# MP3426.net
KiCad netlist of a schematic drawn in EasyEDA Pro
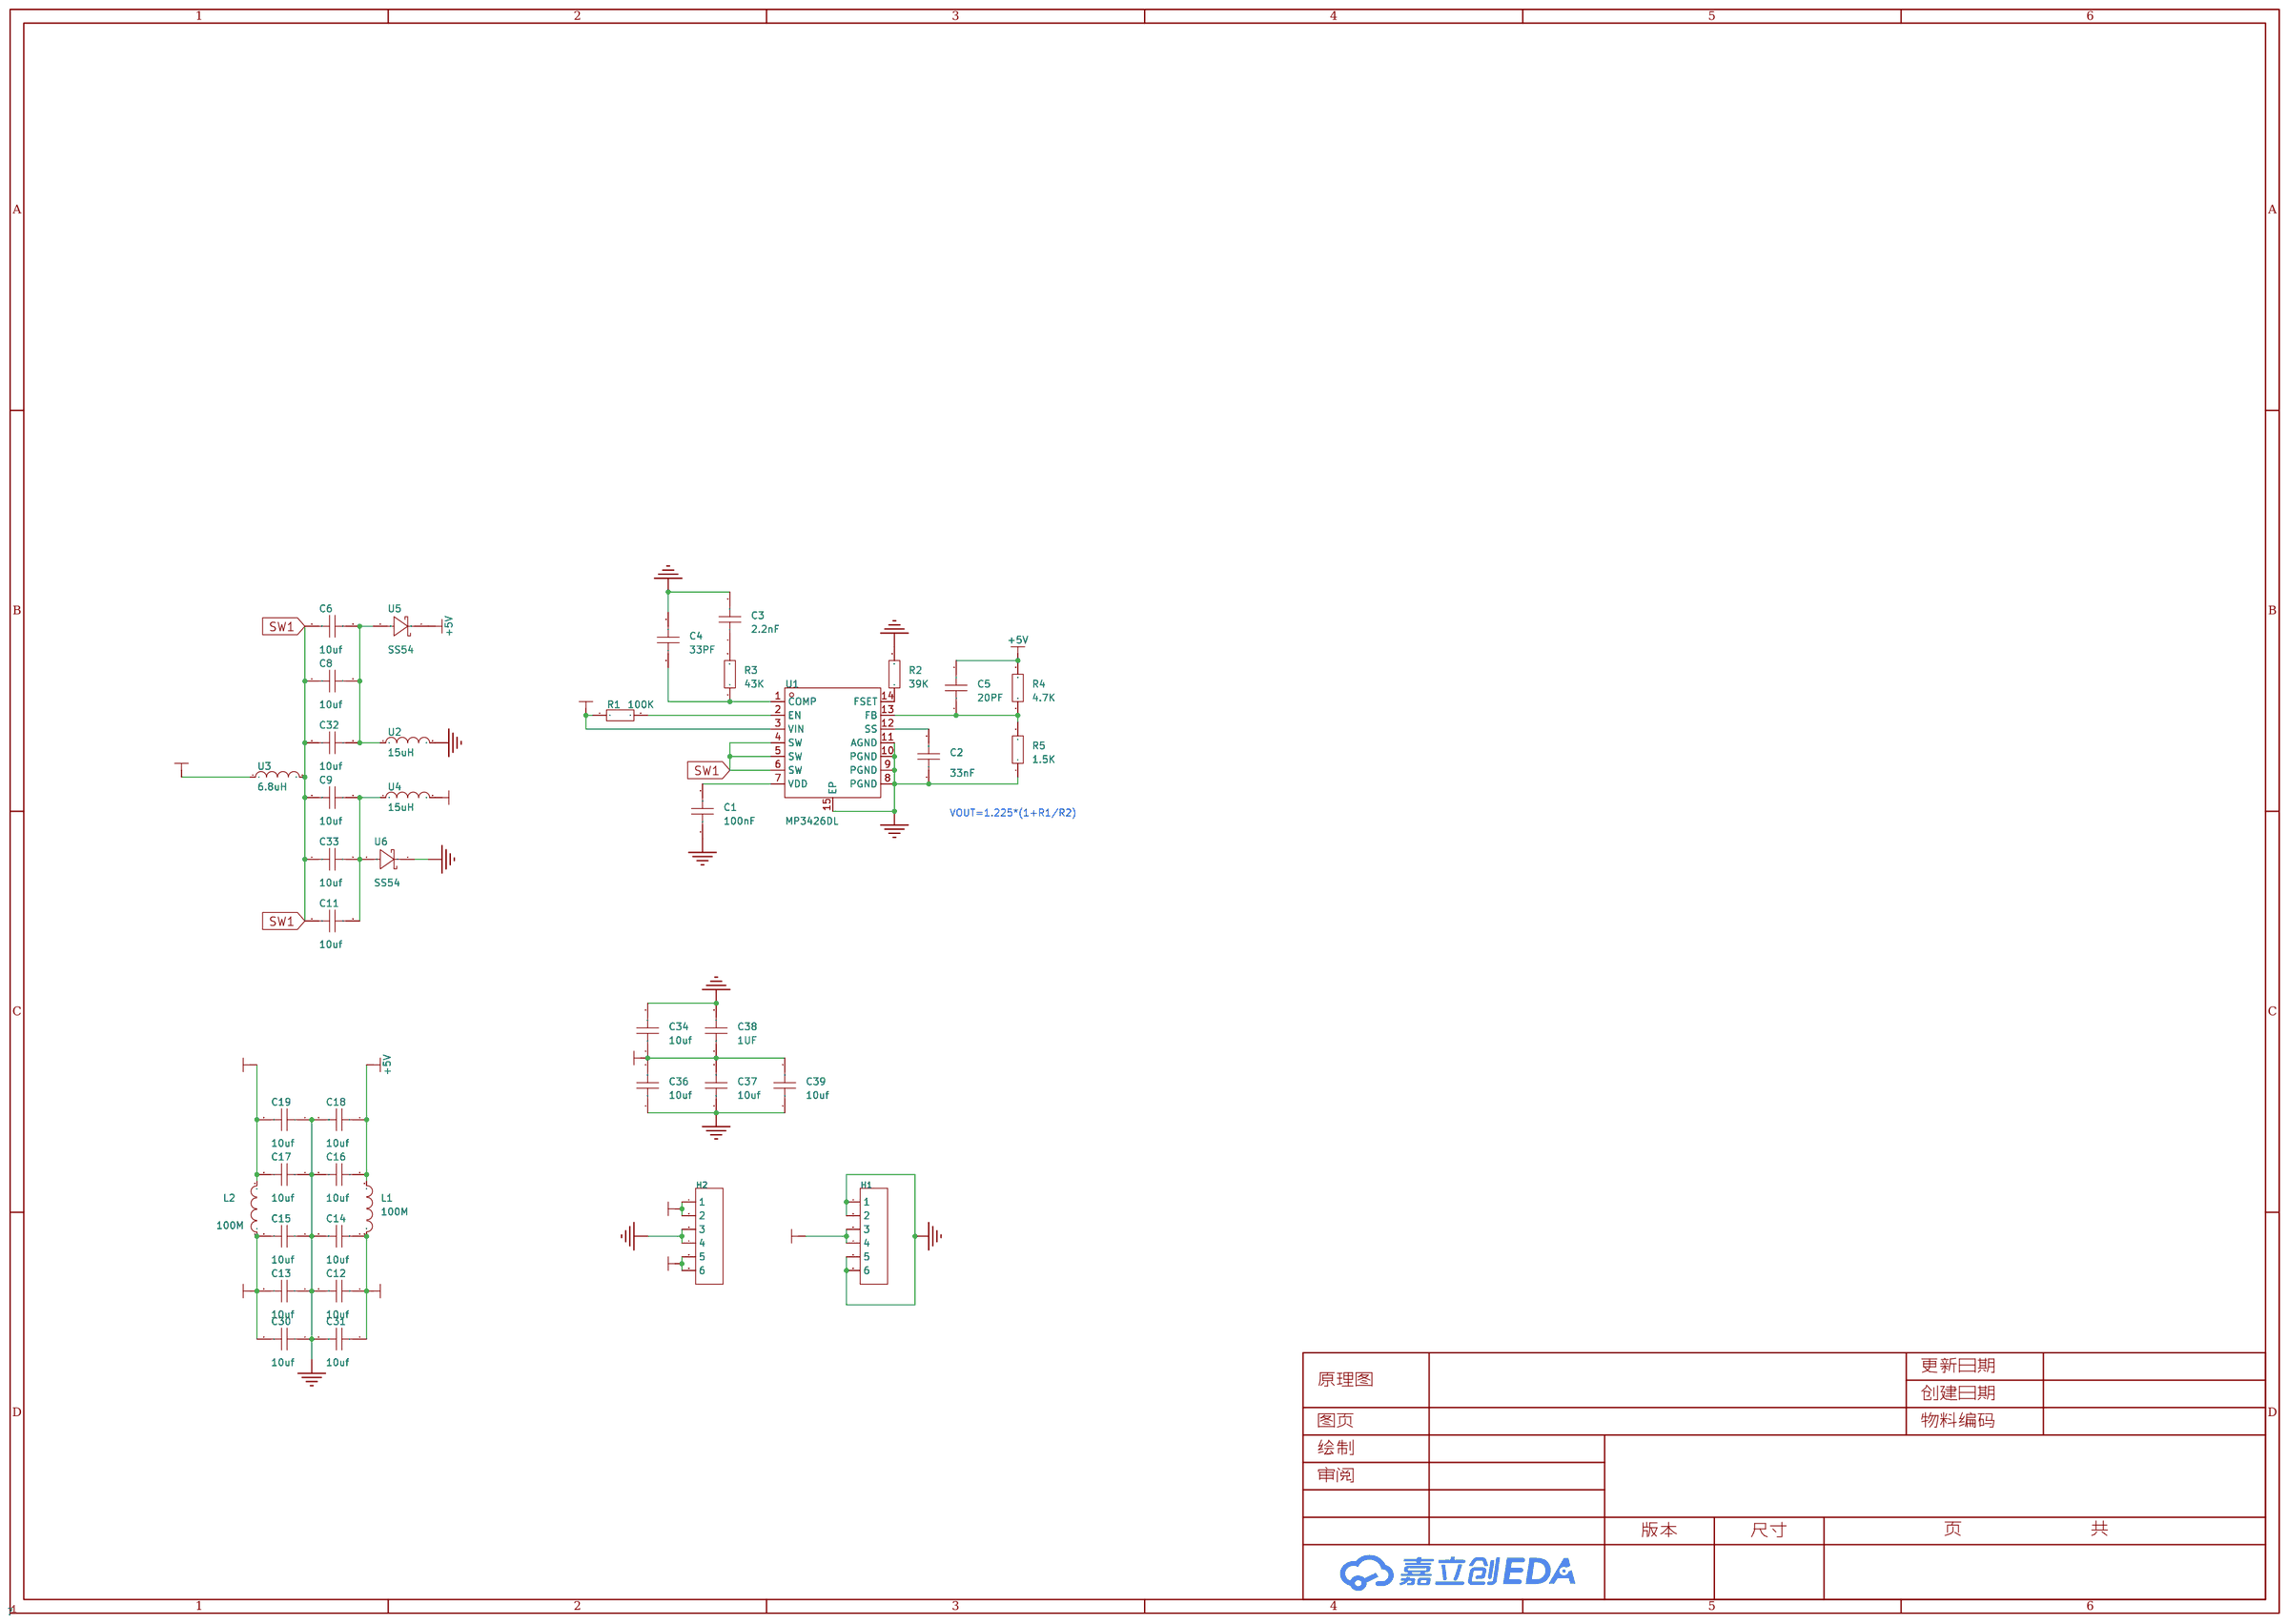
[diagram p0: schematic sheet]

(export (version "E")
  (design (tool "Eeschema 10.0.6"))
  (components
    (comp (ref "C1")
      (value "100nF")
      (footprint "easyedapro:C1206")
      (libsource (lib "easyedapro") (part "CapAcitance"))
    )
    (comp (ref "C2")
      (value "33nF")
      (footprint "easyedapro:C1206")
      (libsource (lib "easyedapro") (part "CapAcitance"))
    )
    (comp (ref "C3")
      (value "2.2nF")
      (footprint "easyedapro:C1206")
      (libsource (lib "easyedapro") (part "CapAcitance"))
    )
    (comp (ref "C4")
      (value "33PF")
      (footprint "easyedapro:C1206")
      (libsource (lib "easyedapro") (part "CapAcitance"))
    )
    (comp (ref "C5")
      (value "20PF")
      (footprint "easyedapro:C1206")
      (libsource (lib "easyedapro") (part "CapAcitance"))
    )
    (comp (ref "C6")
      (value "10uf")
      (footprint "easyedapro:C1206")
      (libsource (lib "easyedapro") (part "CapAcitance"))
    )
    (comp (ref "C8")
      (value "10uf")
      (footprint "easyedapro:C1206")
      (libsource (lib "easyedapro") (part "CapAcitance"))
    )
    (comp (ref "C9")
      (value "10uf")
      (footprint "easyedapro:C1206")
      (libsource (lib "easyedapro") (part "CapAcitance"))
    )
    (comp (ref "C11")
      (value "10uf")
      (footprint "easyedapro:C1206")
      (libsource (lib "easyedapro") (part "CapAcitance"))
    )
    (comp (ref "C12")
      (value "10uf")
      (footprint "easyedapro:C1206")
      (libsource (lib "easyedapro") (part "CapAcitance"))
    )
    (comp (ref "C13")
      (value "10uf")
      (footprint "easyedapro:C1206")
      (libsource (lib "easyedapro") (part "CapAcitance"))
    )
    (comp (ref "C14")
      (value "10uf")
      (footprint "easyedapro:C1206")
      (libsource (lib "easyedapro") (part "CapAcitance"))
    )
    (comp (ref "C15")
      (value "10uf")
      (footprint "easyedapro:C1206")
      (libsource (lib "easyedapro") (part "CapAcitance"))
    )
    (comp (ref "C16")
      (value "10uf")
      (footprint "easyedapro:C1206")
      (libsource (lib "easyedapro") (part "CapAcitance"))
    )
    (comp (ref "C17")
      (value "10uf")
      (footprint "easyedapro:C1206")
      (libsource (lib "easyedapro") (part "CapAcitance"))
    )
    (comp (ref "C18")
      (value "10uf")
      (footprint "easyedapro:C1206")
      (libsource (lib "easyedapro") (part "CapAcitance"))
    )
    (comp (ref "C19")
      (value "10uf")
      (footprint "easyedapro:C1206")
      (libsource (lib "easyedapro") (part "CapAcitance"))
    )
    (comp (ref "C30")
      (value "10uf")
      (footprint "easyedapro:C1206")
      (libsource (lib "easyedapro") (part "CapAcitance"))
    )
    (comp (ref "C31")
      (value "10uf")
      (footprint "easyedapro:C1206")
      (libsource (lib "easyedapro") (part "CapAcitance"))
    )
    (comp (ref "C32")
      (value "10uf")
      (footprint "easyedapro:C1206")
      (libsource (lib "easyedapro") (part "CapAcitance"))
    )
    (comp (ref "C33")
      (value "10uf")
      (footprint "easyedapro:C1206")
      (libsource (lib "easyedapro") (part "CapAcitance"))
    )
    (comp (ref "C34")
      (value "10uf")
      (footprint "easyedapro:C1206")
      (libsource (lib "easyedapro") (part "CapAcitance"))
    )
    (comp (ref "C36")
      (value "10uf")
      (footprint "easyedapro:C1206")
      (libsource (lib "easyedapro") (part "CapAcitance"))
    )
    (comp (ref "C37")
      (value "10uf")
      (footprint "easyedapro:C1206")
      (libsource (lib "easyedapro") (part "CapAcitance"))
    )
    (comp (ref "C38")
      (value "1UF")
      (footprint "easyedapro:C1206")
      (libsource (lib "easyedapro") (part "CapAcitance"))
    )
    (comp (ref "C39")
      (value "10uf")
      (footprint "easyedapro:C1206")
      (libsource (lib "easyedapro") (part "CapAcitance"))
    )
    (comp (ref "H1")
      (value "~")
      (footprint "easyedapro:HDR-TH_6P-P2.54-V-M-1")
      (libsource (lib "easyedapro") (part "Header-Male-2.54_1x6"))
    )
    (comp (ref "H2")
      (value "~")
      (footprint "easyedapro:HDR-TH_6P-P2.54-V-M-1")
      (libsource (lib "easyedapro") (part "Header-Male-2.54_1x6"))
    )
    (comp (ref "L1")
      (value "100M")
      (footprint "easyedapro:L1206")
      (libsource (lib "easyedapro") (part "CMI321609VR27KT"))
    )
    (comp (ref "L2")
      (value "100M")
      (footprint "easyedapro:L1206")
      (libsource (lib "easyedapro") (part "CMI321609VR27KT"))
    )
    (comp (ref "R1") (value "100K") (footprint "easyedapro:R0603") (libsource (lib "easyedapro") (part "电阻")))
    (comp (ref "R2") (value "39K") (footprint "easyedapro:R0603") (libsource (lib "easyedapro") (part "电阻")))
    (comp (ref "R3") (value "43K") (footprint "easyedapro:R0603") (libsource (lib "easyedapro") (part "电阻")))
    (comp (ref "R4") (value "4.7K") (footprint "easyedapro:R0603") (libsource (lib "easyedapro") (part "电阻")))
    (comp (ref "R5") (value "1.5K") (footprint "easyedapro:R0603") (libsource (lib "easyedapro") (part "电阻")))
    (comp (ref "U1")
      (value "MP3426DL")
      (footprint "easyedapro:DFN-14_L4.0-W3.0-P0.50-BL-EP")
      (libsource (lib "easyedapro") (part "MP3426DL"))
    )
    (comp (ref "U2")
      (value "15uH")
      (footprint "easyedapro:IND-SMD_L7.1-W6.6-1")
      (description "电感值:4.7uH;精度:±20%;额定电流:6A;饱和电流(Isat):8A;类型:一体成型电感;")
      (fields
        (field (name "Manufacturer Part") "CXP0650-4R7M-AG(4.7uh)")
        (field (name "Manufacturer") "DMBJ(振宝佳)")
      )
      (libsource (lib "easyedapro") (part "CXP0650-4R7M-AG(4.7UH)"))
    )
    (comp (ref "U3")
      (value "6.8uH")
      (footprint "easyedapro:IND-SMD_L11.0-W10.2")
      (description "电感值:22uH;精度:±20%;额定电流:5.5A;饱和电流(Isat):8A;类型:一体成型电感;")
      (fields
        (field (name "Manufacturer Part") "CXP1050-220M-AG(22uh)")
        (field (name "Manufacturer") "DMBJ(振宝佳)")
      )
      (libsource (lib "easyedapro") (part "CXP1050-220M-AG(22UH)"))
    )
    (comp (ref "U4")
      (value "15uH")
      (footprint "easyedapro:IND-SMD_L7.1-W6.6-1")
      (description "电感值:4.7uH;精度:±20%;额定电流:6A;饱和电流(Isat):8A;类型:一体成型电感;")
      (fields
        (field (name "Manufacturer Part") "CXP0650-4R7M-AG(4.7uh)")
        (field (name "Manufacturer") "DMBJ(振宝佳)")
      )
      (libsource (lib "easyedapro") (part "CXP0650-4R7M-AG(4.7UH)"))
    )
    (comp (ref "U5")
      (value "SS54")
      (footprint "easyedapro:SMB_L4.3-W3.6-LS5.4-RD")
      (description "二极管配置:独立式;正向压降(Vf):550mV@5A;直流反向耐压(Vr):40V;整流电流:5A;")
      (fields (field (name "Manufacturer") "HXY MOSFET(华轩阳电子)"))
      (libsource (lib "easyedapro") (part "SS54_C5200096"))
    )
    (comp (ref "U6")
      (value "SS54")
      (footprint "easyedapro:SMB_L4.3-W3.6-LS5.4-RD")
      (description "二极管配置:独立式;正向压降(Vf):550mV@5A;直流反向耐压(Vr):40V;整流电流:5A;")
      (fields (field (name "Manufacturer") "HXY MOSFET(华轩阳电子)"))
      (libsource (lib "easyedapro") (part "SS54_C5200096"))
    )
  )
  (nets
    (net (code "1") (name "+5V") (class "Default")
      (node (ref "C16") (pin "1") (pinfunction "1_1") (pintype "input"))
      (node (ref "C18") (pin "1") (pinfunction "1_1") (pintype "input"))
      (node (ref "C5") (pin "2") (pinfunction "2_2") (pintype "input"))
      (node (ref "L1") (pin "1") (pinfunction "1_1") (pintype "unspecified"))
      (node (ref "R4") (pin "2") (pinfunction "2_2") (pintype "input"))
      (node (ref "U5") (pin "1") (pinfunction "1_1") (pintype "unspecified"))
    )
    (net (code "2") (name "+5VO") (class "Default")
      (node (ref "C12") (pin "1") (pinfunction "1_1") (pintype "input"))
      (node (ref "C14") (pin "1") (pinfunction "1_1") (pintype "input"))
      (node (ref "C31") (pin "1") (pinfunction "1_1") (pintype "input"))
      (node (ref "H2") (pin "1") (pinfunction "1_1") (pintype "input"))
      (node (ref "H2") (pin "2") (pinfunction "2_2") (pintype "input"))
      (node (ref "L1") (pin "2") (pinfunction "2_2") (pintype "unspecified"))
    )
    (net (code "3") (name "-5V") (class "Default")
      (node (ref "C17") (pin "2") (pinfunction "2_2") (pintype "input"))
      (node (ref "C19") (pin "2") (pinfunction "2_2") (pintype "input"))
      (node (ref "L2") (pin "2") (pinfunction "2_2") (pintype "unspecified"))
      (node (ref "U4") (pin "2") (pinfunction "2_2") (pintype "unspecified"))
    )
    (net (code "4") (name "-5VO") (class "Default")
      (node (ref "C13") (pin "2") (pinfunction "2_2") (pintype "input"))
      (node (ref "C15") (pin "2") (pinfunction "2_2") (pintype "input"))
      (node (ref "C30") (pin "2") (pinfunction "2_2") (pintype "input"))
      (node (ref "H2") (pin "5") (pinfunction "5_5") (pintype "input"))
      (node (ref "H2") (pin "6") (pinfunction "6_6") (pintype "input"))
      (node (ref "L2") (pin "1") (pinfunction "1_1") (pintype "unspecified"))
    )
    (net (code "5") (name "GND") (class "Default")
      (node (ref "C1") (pin "1") (pinfunction "1_1") (pintype "input"))
      (node (ref "C12") (pin "2") (pinfunction "2_2") (pintype "input"))
      (node (ref "C13") (pin "1") (pinfunction "1_1") (pintype "input"))
      (node (ref "C14") (pin "2") (pinfunction "2_2") (pintype "input"))
      (node (ref "C15") (pin "1") (pinfunction "1_1") (pintype "input"))
      (node (ref "C16") (pin "2") (pinfunction "2_2") (pintype "input"))
      (node (ref "C17") (pin "1") (pinfunction "1_1") (pintype "input"))
      (node (ref "C18") (pin "2") (pinfunction "2_2") (pintype "input"))
      (node (ref "C19") (pin "1") (pinfunction "1_1") (pintype "input"))
      (node (ref "C2") (pin "1") (pinfunction "1_1") (pintype "input"))
      (node (ref "C3") (pin "2") (pinfunction "2_2") (pintype "input"))
      (node (ref "C30") (pin "1") (pinfunction "1_1") (pintype "input"))
      (node (ref "C31") (pin "2") (pinfunction "2_2") (pintype "input"))
      (node (ref "C34") (pin "2") (pinfunction "2_2") (pintype "input"))
      (node (ref "C36") (pin "1") (pinfunction "1_1") (pintype "input"))
      (node (ref "C37") (pin "1") (pinfunction "1_1") (pintype "input"))
      (node (ref "C38") (pin "2") (pinfunction "2_2") (pintype "input"))
      (node (ref "C39") (pin "1") (pinfunction "1_1") (pintype "input"))
      (node (ref "C4") (pin "2") (pinfunction "2_2") (pintype "input"))
      (node (ref "H1") (pin "1") (pinfunction "1_1") (pintype "input"))
      (node (ref "H1") (pin "2") (pinfunction "2_2") (pintype "input"))
      (node (ref "H1") (pin "5") (pinfunction "5_5") (pintype "input"))
      (node (ref "H1") (pin "6") (pinfunction "6_6") (pintype "input"))
      (node (ref "H2") (pin "3") (pinfunction "3_3") (pintype "input"))
      (node (ref "H2") (pin "4") (pinfunction "4_4") (pintype "input"))
      (node (ref "R2") (pin "2") (pinfunction "2_2") (pintype "input"))
      (node (ref "R5") (pin "1") (pinfunction "1_1") (pintype "input"))
      (node (ref "U1") (pin "10") (pinfunction "PGND_10") (pintype "input"))
      (node (ref "U1") (pin "11") (pinfunction "AGND_11") (pintype "input"))
      (node (ref "U1") (pin "15") (pinfunction "EP_15") (pintype "input"))
      (node (ref "U1") (pin "8") (pinfunction "PGND_8") (pintype "input"))
      (node (ref "U1") (pin "9") (pinfunction "PGND_9") (pintype "input"))
      (node (ref "U2") (pin "2") (pinfunction "2_2") (pintype "unspecified"))
      (node (ref "U6") (pin "1") (pinfunction "1_1") (pintype "unspecified"))
    )
    (net (code "6") (name "Net-(C3-Pad1)") (class "Default")
      (node (ref "C3") (pin "1") (pinfunction "1_1") (pintype "input"))
      (node (ref "R3") (pin "2") (pinfunction "2_2") (pintype "input"))
    )
    (net (code "7") (name "Net-(C11-Pad2)") (class "Default")
      (node (ref "C11") (pin "2") (pinfunction "2_2") (pintype "input"))
      (node (ref "C33") (pin "2") (pinfunction "2_2") (pintype "input"))
      (node (ref "C9") (pin "2") (pinfunction "2_2") (pintype "input"))
      (node (ref "U4") (pin "1") (pinfunction "1_1") (pintype "unspecified"))
      (node (ref "U6") (pin "2") (pinfunction "2_2") (pintype "unspecified"))
    )
    (net (code "8") (name "Net-(C32-Pad2)") (class "Default")
      (node (ref "C32") (pin "2") (pinfunction "2_2") (pintype "input"))
      (node (ref "C6") (pin "2") (pinfunction "2_2") (pintype "input"))
      (node (ref "C8") (pin "2") (pinfunction "2_2") (pintype "input"))
      (node (ref "U2") (pin "1") (pinfunction "1_1") (pintype "unspecified"))
      (node (ref "U5") (pin "2") (pinfunction "2_2") (pintype "unspecified"))
    )
    (net (code "9") (name "Net-(U1-COMP)") (class "Default")
      (node (ref "C4") (pin "1") (pinfunction "1_1") (pintype "input"))
      (node (ref "R3") (pin "1") (pinfunction "1_1") (pintype "input"))
      (node (ref "U1") (pin "1") (pinfunction "COMP_1") (pintype "input"))
    )
    (net (code "10") (name "Net-(U1-EN)") (class "Default")
      (node (ref "R1") (pin "2") (pinfunction "2_2") (pintype "input"))
      (node (ref "U1") (pin "2") (pinfunction "EN_2") (pintype "input"))
    )
    (net (code "11") (name "Net-(U1-FB)") (class "Default")
      (node (ref "C5") (pin "1") (pinfunction "1_1") (pintype "input"))
      (node (ref "R4") (pin "1") (pinfunction "1_1") (pintype "input"))
      (node (ref "R5") (pin "2") (pinfunction "2_2") (pintype "input"))
      (node (ref "U1") (pin "13") (pinfunction "FB_13") (pintype "input"))
    )
    (net (code "12") (name "Net-(U1-FSET)") (class "Default")
      (node (ref "R2") (pin "1") (pinfunction "1_1") (pintype "input"))
      (node (ref "U1") (pin "14") (pinfunction "FSET_14") (pintype "input"))
    )
    (net (code "13") (name "Net-(U1-SS)") (class "Default")
      (node (ref "C2") (pin "2") (pinfunction "2_2") (pintype "input"))
      (node (ref "U1") (pin "12") (pinfunction "SS_12") (pintype "input"))
    )
    (net (code "14") (name "Net-(U1-VDD)") (class "Default")
      (node (ref "C1") (pin "2") (pinfunction "2_2") (pintype "input"))
      (node (ref "U1") (pin "7") (pinfunction "VDD_7") (pintype "input"))
    )
    (net (code "15") (name "SW1") (class "Default")
      (node (ref "C11") (pin "1") (pinfunction "1_1") (pintype "input"))
      (node (ref "C32") (pin "1") (pinfunction "1_1") (pintype "input"))
      (node (ref "C33") (pin "1") (pinfunction "1_1") (pintype "input"))
      (node (ref "C6") (pin "1") (pinfunction "1_1") (pintype "input"))
      (node (ref "C8") (pin "1") (pinfunction "1_1") (pintype "input"))
      (node (ref "C9") (pin "1") (pinfunction "1_1") (pintype "input"))
      (node (ref "U1") (pin "4") (pinfunction "SW_4") (pintype "input"))
      (node (ref "U1") (pin "5") (pinfunction "SW_5") (pintype "input"))
      (node (ref "U1") (pin "6") (pinfunction "SW_6") (pintype "input"))
      (node (ref "U3") (pin "2") (pinfunction "2_2") (pintype "unspecified"))
    )
    (net (code "16") (name "VIN") (class "Default")
      (node (ref "C34") (pin "1") (pinfunction "1_1") (pintype "input"))
      (node (ref "C36") (pin "2") (pinfunction "2_2") (pintype "input"))
      (node (ref "C37") (pin "2") (pinfunction "2_2") (pintype "input"))
      (node (ref "C38") (pin "1") (pinfunction "1_1") (pintype "input"))
      (node (ref "C39") (pin "2") (pinfunction "2_2") (pintype "input"))
      (node (ref "H1") (pin "3") (pinfunction "3_3") (pintype "input"))
      (node (ref "H1") (pin "4") (pinfunction "4_4") (pintype "input"))
      (node (ref "R1") (pin "1") (pinfunction "1_1") (pintype "input"))
      (node (ref "U1") (pin "3") (pinfunction "VIN_3") (pintype "input"))
      (node (ref "U3") (pin "1") (pinfunction "1_1") (pintype "unspecified"))
    )
  )
)
